# 7seg_Buttons.net
KiCad netlist of a schematic drawn in EAGLE
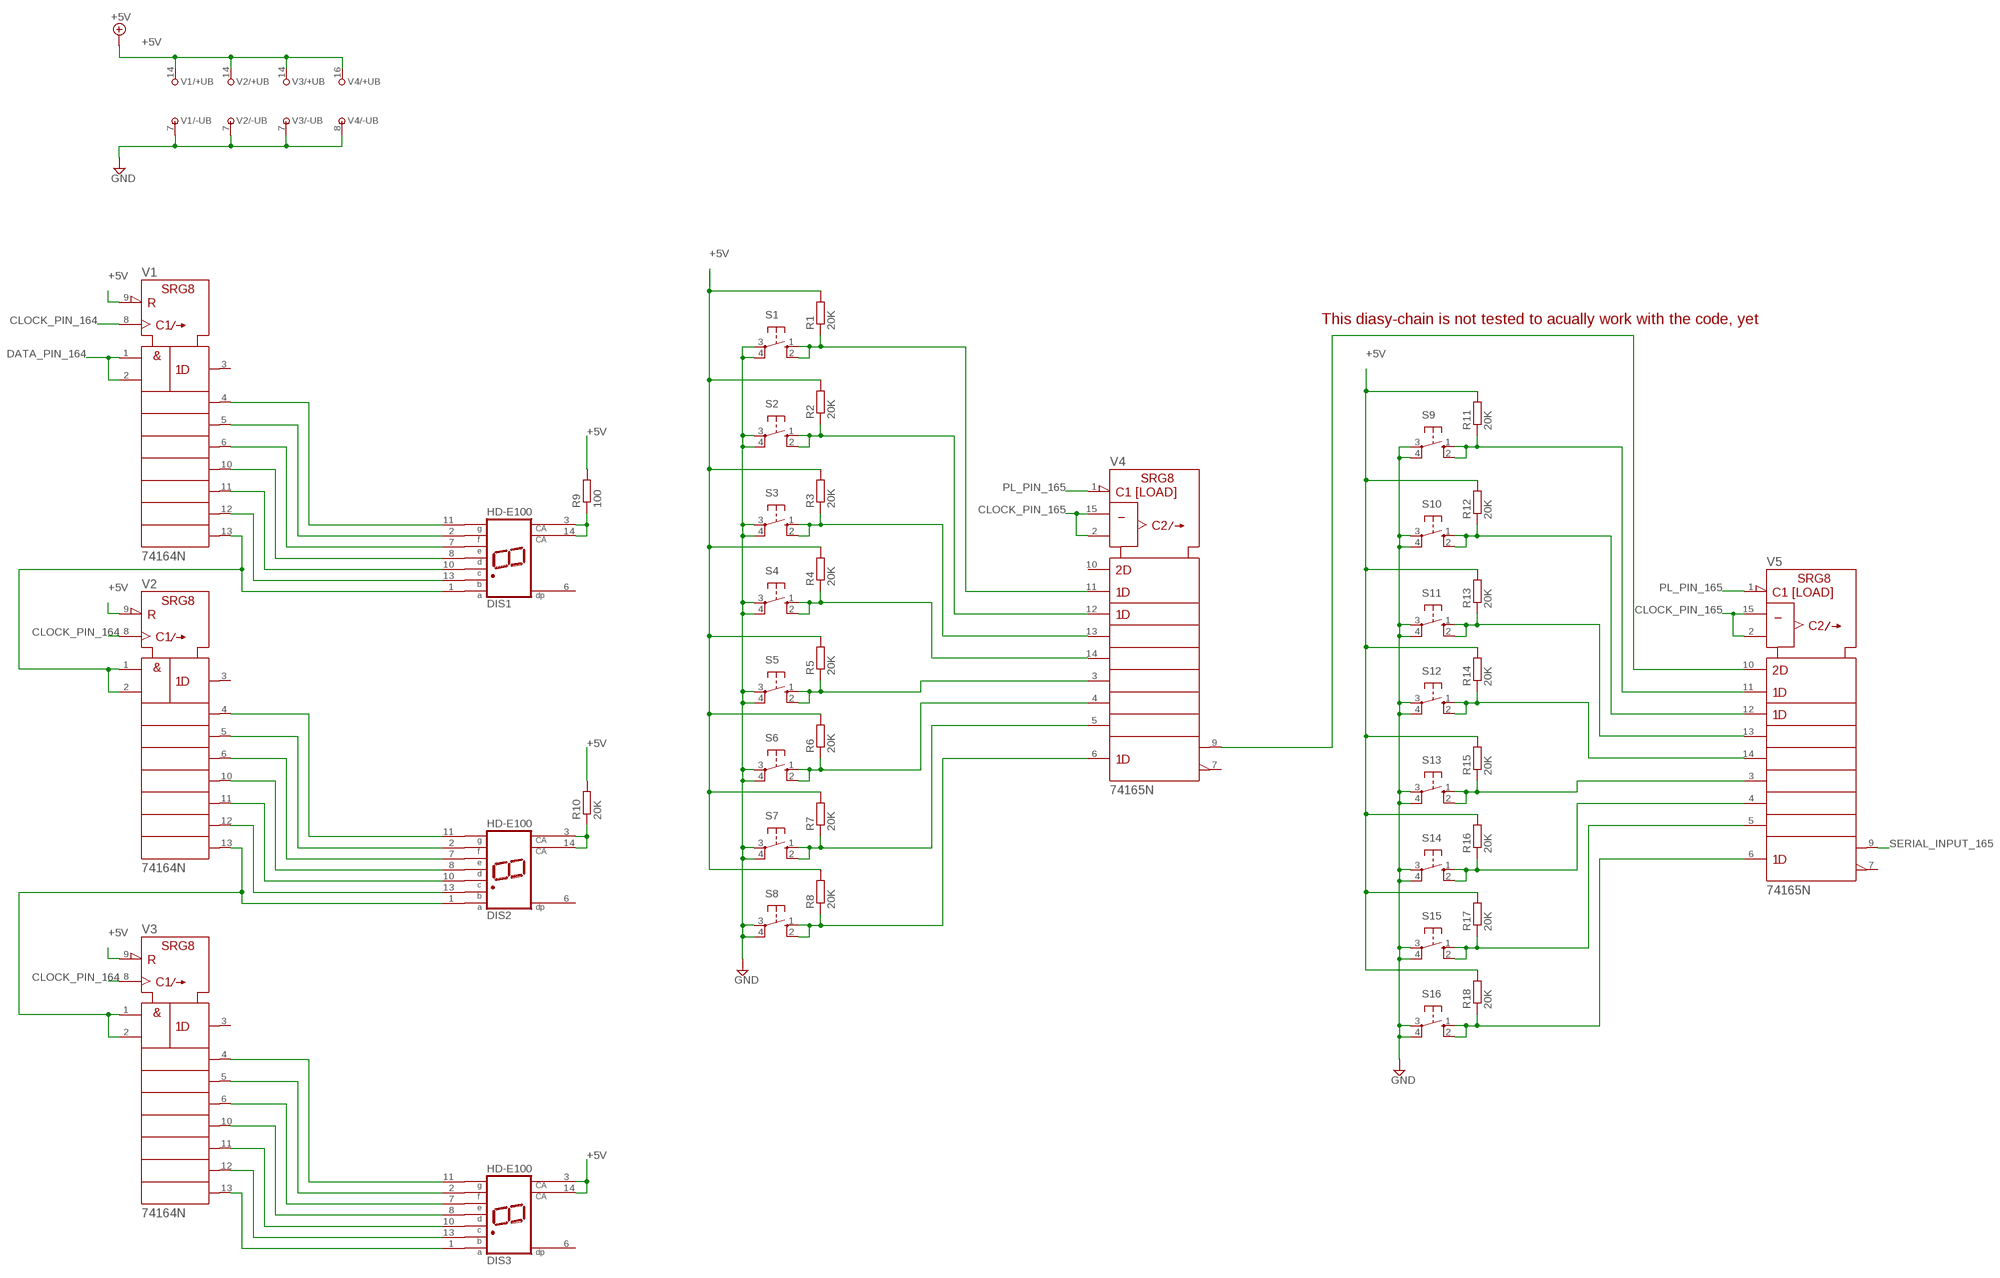
[diagram p0: schematic, sheet 1]

(export (version "E")
  (design (tool "Eeschema 10.0.6"))
  (components
    (comp (ref "DIS1")
      (value "HD-E100")
      (footprint "eagle-import:HDSP-I")
      (libsource (lib "eagle-import") (part "HD-E100"))
    )
    (comp (ref "DIS2")
      (value "HD-E100")
      (footprint "eagle-import:HDSP-I")
      (libsource (lib "eagle-import") (part "HD-E100"))
    )
    (comp (ref "DIS3")
      (value "HD-E100")
      (footprint "eagle-import:HDSP-I")
      (libsource (lib "eagle-import") (part "HD-E100"))
    )
    (comp (ref "R1")
      (value "20K")
      (footprint "eagle-import:0204_7")
      (libsource (lib "eagle-import") (part "R-EU_0204/7"))
    )
    (comp (ref "R2")
      (value "20K")
      (footprint "eagle-import:0204_7")
      (libsource (lib "eagle-import") (part "R-EU_0204/7"))
    )
    (comp (ref "R3")
      (value "20K")
      (footprint "eagle-import:0204_7")
      (libsource (lib "eagle-import") (part "R-EU_0204/7"))
    )
    (comp (ref "R4")
      (value "20K")
      (footprint "eagle-import:0204_7")
      (libsource (lib "eagle-import") (part "R-EU_0204/7"))
    )
    (comp (ref "R5")
      (value "20K")
      (footprint "eagle-import:0204_7")
      (libsource (lib "eagle-import") (part "R-EU_0204/7"))
    )
    (comp (ref "R6")
      (value "20K")
      (footprint "eagle-import:0204_7")
      (libsource (lib "eagle-import") (part "R-EU_0204/7"))
    )
    (comp (ref "R7")
      (value "20K")
      (footprint "eagle-import:0204_7")
      (libsource (lib "eagle-import") (part "R-EU_0204/7"))
    )
    (comp (ref "R8")
      (value "20K")
      (footprint "eagle-import:0204_7")
      (libsource (lib "eagle-import") (part "R-EU_0204/7"))
    )
    (comp (ref "R9")
      (value "100")
      (footprint "eagle-import:0204_7")
      (libsource (lib "eagle-import") (part "R-EU_0204/7"))
    )
    (comp (ref "R10")
      (value "20K")
      (footprint "eagle-import:0204_7")
      (libsource (lib "eagle-import") (part "R-EU_0204/7"))
    )
    (comp (ref "R11")
      (value "20K")
      (footprint "eagle-import:0204_7")
      (libsource (lib "eagle-import") (part "R-EU_0204/7"))
    )
    (comp (ref "R12")
      (value "20K")
      (footprint "eagle-import:0204_7")
      (libsource (lib "eagle-import") (part "R-EU_0204/7"))
    )
    (comp (ref "R13")
      (value "20K")
      (footprint "eagle-import:0204_7")
      (libsource (lib "eagle-import") (part "R-EU_0204/7"))
    )
    (comp (ref "R14")
      (value "20K")
      (footprint "eagle-import:0204_7")
      (libsource (lib "eagle-import") (part "R-EU_0204/7"))
    )
    (comp (ref "R15")
      (value "20K")
      (footprint "eagle-import:0204_7")
      (libsource (lib "eagle-import") (part "R-EU_0204/7"))
    )
    (comp (ref "R16")
      (value "20K")
      (footprint "eagle-import:0204_7")
      (libsource (lib "eagle-import") (part "R-EU_0204/7"))
    )
    (comp (ref "R17")
      (value "20K")
      (footprint "eagle-import:0204_7")
      (libsource (lib "eagle-import") (part "R-EU_0204/7"))
    )
    (comp (ref "R18")
      (value "20K")
      (footprint "eagle-import:0204_7")
      (libsource (lib "eagle-import") (part "R-EU_0204/7"))
    )
    (comp (ref "S1")
      (value "40-XX")
      (footprint "eagle-import:B3F-40XX")
      (fields (field (name "MF") "OMRON COMPONENTS USA") (field (name "MPN") "B3F-4000"))
      (libsource (lib "eagle-import") (part "40-XX"))
    )
    (comp (ref "S2")
      (value "40-XX")
      (footprint "eagle-import:B3F-40XX")
      (fields (field (name "MF") "OMRON COMPONENTS USA") (field (name "MPN") "B3F-4000"))
      (libsource (lib "eagle-import") (part "40-XX"))
    )
    (comp (ref "S3")
      (value "40-XX")
      (footprint "eagle-import:B3F-40XX")
      (fields (field (name "MF") "OMRON COMPONENTS USA") (field (name "MPN") "B3F-4000"))
      (libsource (lib "eagle-import") (part "40-XX"))
    )
    (comp (ref "S4")
      (value "40-XX")
      (footprint "eagle-import:B3F-40XX")
      (fields (field (name "MF") "OMRON COMPONENTS USA") (field (name "MPN") "B3F-4000"))
      (libsource (lib "eagle-import") (part "40-XX"))
    )
    (comp (ref "S5")
      (value "40-XX")
      (footprint "eagle-import:B3F-40XX")
      (fields (field (name "MF") "OMRON COMPONENTS USA") (field (name "MPN") "B3F-4000"))
      (libsource (lib "eagle-import") (part "40-XX"))
    )
    (comp (ref "S6")
      (value "40-XX")
      (footprint "eagle-import:B3F-40XX")
      (fields (field (name "MF") "OMRON COMPONENTS USA") (field (name "MPN") "B3F-4000"))
      (libsource (lib "eagle-import") (part "40-XX"))
    )
    (comp (ref "S7")
      (value "40-XX")
      (footprint "eagle-import:B3F-40XX")
      (fields (field (name "MF") "OMRON COMPONENTS USA") (field (name "MPN") "B3F-4000"))
      (libsource (lib "eagle-import") (part "40-XX"))
    )
    (comp (ref "S8")
      (value "40-XX")
      (footprint "eagle-import:B3F-40XX")
      (fields (field (name "MF") "OMRON COMPONENTS USA") (field (name "MPN") "B3F-4000"))
      (libsource (lib "eagle-import") (part "40-XX"))
    )
    (comp (ref "S9")
      (value "40-XX")
      (footprint "eagle-import:B3F-40XX")
      (fields (field (name "MF") "OMRON COMPONENTS USA") (field (name "MPN") "B3F-4000"))
      (libsource (lib "eagle-import") (part "40-XX"))
    )
    (comp (ref "S10")
      (value "40-XX")
      (footprint "eagle-import:B3F-40XX")
      (fields (field (name "MF") "OMRON COMPONENTS USA") (field (name "MPN") "B3F-4000"))
      (libsource (lib "eagle-import") (part "40-XX"))
    )
    (comp (ref "S11")
      (value "40-XX")
      (footprint "eagle-import:B3F-40XX")
      (fields (field (name "MF") "OMRON COMPONENTS USA") (field (name "MPN") "B3F-4000"))
      (libsource (lib "eagle-import") (part "40-XX"))
    )
    (comp (ref "S12")
      (value "40-XX")
      (footprint "eagle-import:B3F-40XX")
      (fields (field (name "MF") "OMRON COMPONENTS USA") (field (name "MPN") "B3F-4000"))
      (libsource (lib "eagle-import") (part "40-XX"))
    )
    (comp (ref "S13")
      (value "40-XX")
      (footprint "eagle-import:B3F-40XX")
      (fields (field (name "MF") "OMRON COMPONENTS USA") (field (name "MPN") "B3F-4000"))
      (libsource (lib "eagle-import") (part "40-XX"))
    )
    (comp (ref "S14")
      (value "40-XX")
      (footprint "eagle-import:B3F-40XX")
      (fields (field (name "MF") "OMRON COMPONENTS USA") (field (name "MPN") "B3F-4000"))
      (libsource (lib "eagle-import") (part "40-XX"))
    )
    (comp (ref "S15")
      (value "40-XX")
      (footprint "eagle-import:B3F-40XX")
      (fields (field (name "MF") "OMRON COMPONENTS USA") (field (name "MPN") "B3F-4000"))
      (libsource (lib "eagle-import") (part "40-XX"))
    )
    (comp (ref "S16")
      (value "40-XX")
      (footprint "eagle-import:B3F-40XX")
      (fields (field (name "MF") "OMRON COMPONENTS USA") (field (name "MPN") "B3F-4000"))
      (libsource (lib "eagle-import") (part "40-XX"))
    )
    (comp (ref "V1")
      (value "74164N")
      (footprint "eagle-import:DIL14")
      (libsource (lib "eagle-import") (part "74164N"))
    )
    (comp (ref "V2")
      (value "74164N")
      (footprint "eagle-import:DIL14")
      (libsource (lib "eagle-import") (part "74164N"))
    )
    (comp (ref "V3")
      (value "74164N")
      (footprint "eagle-import:DIL14")
      (libsource (lib "eagle-import") (part "74164N"))
    )
    (comp (ref "V4")
      (value "74165N")
      (footprint "eagle-import:DIL16")
      (libsource (lib "eagle-import") (part "74165N"))
    )
    (comp (ref "V5")
      (value "74165N")
      (footprint "eagle-import:DIL16")
      (libsource (lib "eagle-import") (part "74165N"))
    )
  )
  (nets
    (net (code "1") (name "+5V") (class "Default")
      (node (ref "DIS3") (pin "14") (pinfunction "CA_14") (pintype "passive"))
      (node (ref "DIS3") (pin "3") (pinfunction "CA_3") (pintype "passive"))
      (node (ref "R1") (pin "2") (pinfunction "2_2") (pintype "passive"))
      (node (ref "R10") (pin "2") (pinfunction "2_2") (pintype "passive"))
      (node (ref "R11") (pin "2") (pinfunction "2_2") (pintype "passive"))
      (node (ref "R12") (pin "2") (pinfunction "2_2") (pintype "passive"))
      (node (ref "R13") (pin "2") (pinfunction "2_2") (pintype "passive"))
      (node (ref "R14") (pin "2") (pinfunction "2_2") (pintype "passive"))
      (node (ref "R15") (pin "2") (pinfunction "2_2") (pintype "passive"))
      (node (ref "R16") (pin "2") (pinfunction "2_2") (pintype "passive"))
      (node (ref "R17") (pin "2") (pinfunction "2_2") (pintype "passive"))
      (node (ref "R18") (pin "2") (pinfunction "2_2") (pintype "passive"))
      (node (ref "R2") (pin "2") (pinfunction "2_2") (pintype "passive"))
      (node (ref "R3") (pin "2") (pinfunction "2_2") (pintype "passive"))
      (node (ref "R4") (pin "2") (pinfunction "2_2") (pintype "passive"))
      (node (ref "R5") (pin "2") (pinfunction "2_2") (pintype "passive"))
      (node (ref "R6") (pin "2") (pinfunction "2_2") (pintype "passive"))
      (node (ref "R7") (pin "2") (pinfunction "2_2") (pintype "passive"))
      (node (ref "R8") (pin "2") (pinfunction "2_2") (pintype "passive"))
      (node (ref "R9") (pin "2") (pinfunction "2_2") (pintype "passive"))
      (node (ref "V1") (pin "14") (pinfunction "+UB_14") (pintype "power_in"))
      (node (ref "V1") (pin "9") (pinfunction "~{CLR}_9") (pintype "input"))
      (node (ref "V2") (pin "14") (pinfunction "+UB_14") (pintype "power_in"))
      (node (ref "V2") (pin "9") (pinfunction "~{CLR}_9") (pintype "input"))
      (node (ref "V3") (pin "14") (pinfunction "+UB_14") (pintype "power_in"))
      (node (ref "V3") (pin "9") (pinfunction "~{CLR}_9") (pintype "input"))
      (node (ref "V4") (pin "16") (pinfunction "+UB_16") (pintype "power_in"))
    )
    (net (code "2") (name "/CLOCK_PIN_164") (class "Default")
      (node (ref "V1") (pin "8") (pinfunction "CLK_8") (pintype "input"))
      (node (ref "V2") (pin "8") (pinfunction "CLK_8") (pintype "input"))
      (node (ref "V3") (pin "8") (pinfunction "CLK_8") (pintype "input"))
    )
    (net (code "3") (name "/CLOCK_PIN_165") (class "Default")
      (node (ref "V4") (pin "15") (pinfunction "CLK_INH_15") (pintype "input"))
      (node (ref "V4") (pin "2") (pinfunction "CLK_2") (pintype "input"))
      (node (ref "V5") (pin "15") (pinfunction "CLK_INH_15") (pintype "input"))
      (node (ref "V5") (pin "2") (pinfunction "CLK_2") (pintype "input"))
    )
    (net (code "4") (name "/DATA_PIN_164") (class "Default")
      (node (ref "V1") (pin "1") (pinfunction "A_1") (pintype "input"))
      (node (ref "V1") (pin "2") (pinfunction "B_2") (pintype "input"))
    )
    (net (code "5") (name "/PL_PIN_165") (class "Default")
      (node (ref "V4") (pin "1") (pinfunction "SH/~{LD}_1") (pintype "input"))
      (node (ref "V5") (pin "1") (pinfunction "SH/~{LD}_1") (pintype "input"))
    )
    (net (code "6") (name "/SERIAL_INPUT_165") (class "Default")
      (node (ref "V5") (pin "9") (pinfunction "QH_9") (pintype "output"))
    )
    (net (code "7") (name "GND") (class "Default")
      (node (ref "S1") (pin "3") (pinfunction "P_3") (pintype "passive"))
      (node (ref "S1") (pin "4") (pinfunction "P1_4") (pintype "passive"))
      (node (ref "S10") (pin "3") (pinfunction "P_3") (pintype "passive"))
      (node (ref "S10") (pin "4") (pinfunction "P1_4") (pintype "passive"))
      (node (ref "S11") (pin "3") (pinfunction "P_3") (pintype "passive"))
      (node (ref "S11") (pin "4") (pinfunction "P1_4") (pintype "passive"))
      (node (ref "S12") (pin "3") (pinfunction "P_3") (pintype "passive"))
      (node (ref "S12") (pin "4") (pinfunction "P1_4") (pintype "passive"))
      (node (ref "S13") (pin "3") (pinfunction "P_3") (pintype "passive"))
      (node (ref "S13") (pin "4") (pinfunction "P1_4") (pintype "passive"))
      (node (ref "S14") (pin "3") (pinfunction "P_3") (pintype "passive"))
      (node (ref "S14") (pin "4") (pinfunction "P1_4") (pintype "passive"))
      (node (ref "S15") (pin "3") (pinfunction "P_3") (pintype "passive"))
      (node (ref "S15") (pin "4") (pinfunction "P1_4") (pintype "passive"))
      (node (ref "S16") (pin "3") (pinfunction "P_3") (pintype "passive"))
      (node (ref "S16") (pin "4") (pinfunction "P1_4") (pintype "passive"))
      (node (ref "S2") (pin "3") (pinfunction "P_3") (pintype "passive"))
      (node (ref "S2") (pin "4") (pinfunction "P1_4") (pintype "passive"))
      (node (ref "S3") (pin "3") (pinfunction "P_3") (pintype "passive"))
      (node (ref "S3") (pin "4") (pinfunction "P1_4") (pintype "passive"))
      (node (ref "S4") (pin "3") (pinfunction "P_3") (pintype "passive"))
      (node (ref "S4") (pin "4") (pinfunction "P1_4") (pintype "passive"))
      (node (ref "S5") (pin "3") (pinfunction "P_3") (pintype "passive"))
      (node (ref "S5") (pin "4") (pinfunction "P1_4") (pintype "passive"))
      (node (ref "S6") (pin "3") (pinfunction "P_3") (pintype "passive"))
      (node (ref "S6") (pin "4") (pinfunction "P1_4") (pintype "passive"))
      (node (ref "S7") (pin "3") (pinfunction "P_3") (pintype "passive"))
      (node (ref "S7") (pin "4") (pinfunction "P1_4") (pintype "passive"))
      (node (ref "S8") (pin "3") (pinfunction "P_3") (pintype "passive"))
      (node (ref "S8") (pin "4") (pinfunction "P1_4") (pintype "passive"))
      (node (ref "S9") (pin "3") (pinfunction "P_3") (pintype "passive"))
      (node (ref "S9") (pin "4") (pinfunction "P1_4") (pintype "passive"))
      (node (ref "V1") (pin "7") (pinfunction "-UB_7") (pintype "power_in"))
      (node (ref "V2") (pin "7") (pinfunction "-UB_7") (pintype "power_in"))
      (node (ref "V3") (pin "7") (pinfunction "-UB_7") (pintype "power_in"))
      (node (ref "V4") (pin "8") (pinfunction "-UB_8") (pintype "power_in"))
    )
    (net (code "8") (name "Net-(DIS1-A)") (class "Default")
      (node (ref "DIS1") (pin "1") (pinfunction "A_1") (pintype "passive"))
      (node (ref "V1") (pin "13") (pinfunction "QH_13") (pintype "output"))
      (node (ref "V2") (pin "1") (pinfunction "A_1") (pintype "input"))
      (node (ref "V2") (pin "2") (pinfunction "B_2") (pintype "input"))
    )
    (net (code "9") (name "Net-(DIS1-B)") (class "Default")
      (node (ref "DIS1") (pin "13") (pinfunction "B_13") (pintype "passive"))
      (node (ref "V1") (pin "12") (pinfunction "QG_12") (pintype "output"))
    )
    (net (code "10") (name "Net-(DIS1-C)") (class "Default")
      (node (ref "DIS1") (pin "10") (pinfunction "C_10") (pintype "passive"))
      (node (ref "V1") (pin "11") (pinfunction "QF_11") (pintype "output"))
    )
    (net (code "11") (name "Net-(DIS1-CA-Pad14)") (class "Default")
      (node (ref "DIS1") (pin "14") (pinfunction "CA_14") (pintype "passive"))
      (node (ref "DIS1") (pin "3") (pinfunction "CA_3") (pintype "passive"))
      (node (ref "R9") (pin "1") (pinfunction "1_1") (pintype "passive"))
    )
    (net (code "12") (name "Net-(DIS1-D)") (class "Default")
      (node (ref "DIS1") (pin "8") (pinfunction "D_8") (pintype "passive"))
      (node (ref "V1") (pin "10") (pinfunction "QE_10") (pintype "output"))
    )
    (net (code "13") (name "Net-(DIS1-E)") (class "Default")
      (node (ref "DIS1") (pin "7") (pinfunction "E_7") (pintype "passive"))
      (node (ref "V1") (pin "6") (pinfunction "QD_6") (pintype "output"))
    )
    (net (code "14") (name "Net-(DIS1-F)") (class "Default")
      (node (ref "DIS1") (pin "2") (pinfunction "F_2") (pintype "passive"))
      (node (ref "V1") (pin "5") (pinfunction "QC_5") (pintype "output"))
    )
    (net (code "15") (name "Net-(DIS1-G)") (class "Default")
      (node (ref "DIS1") (pin "11") (pinfunction "G_11") (pintype "passive"))
      (node (ref "V1") (pin "4") (pinfunction "QB_4") (pintype "output"))
    )
    (net (code "16") (name "Net-(DIS2-A)") (class "Default")
      (node (ref "DIS2") (pin "1") (pinfunction "A_1") (pintype "passive"))
      (node (ref "V2") (pin "13") (pinfunction "QH_13") (pintype "output"))
      (node (ref "V3") (pin "1") (pinfunction "A_1") (pintype "input"))
      (node (ref "V3") (pin "2") (pinfunction "B_2") (pintype "input"))
    )
    (net (code "17") (name "Net-(DIS2-B)") (class "Default")
      (node (ref "DIS2") (pin "13") (pinfunction "B_13") (pintype "passive"))
      (node (ref "V2") (pin "12") (pinfunction "QG_12") (pintype "output"))
    )
    (net (code "18") (name "Net-(DIS2-C)") (class "Default")
      (node (ref "DIS2") (pin "10") (pinfunction "C_10") (pintype "passive"))
      (node (ref "V2") (pin "11") (pinfunction "QF_11") (pintype "output"))
    )
    (net (code "19") (name "Net-(DIS2-CA-Pad14)") (class "Default")
      (node (ref "DIS2") (pin "14") (pinfunction "CA_14") (pintype "passive"))
      (node (ref "DIS2") (pin "3") (pinfunction "CA_3") (pintype "passive"))
      (node (ref "R10") (pin "1") (pinfunction "1_1") (pintype "passive"))
    )
    (net (code "20") (name "Net-(DIS2-D)") (class "Default")
      (node (ref "DIS2") (pin "8") (pinfunction "D_8") (pintype "passive"))
      (node (ref "V2") (pin "10") (pinfunction "QE_10") (pintype "output"))
    )
    (net (code "21") (name "Net-(DIS2-E)") (class "Default")
      (node (ref "DIS2") (pin "7") (pinfunction "E_7") (pintype "passive"))
      (node (ref "V2") (pin "6") (pinfunction "QD_6") (pintype "output"))
    )
    (net (code "22") (name "Net-(DIS2-F)") (class "Default")
      (node (ref "DIS2") (pin "2") (pinfunction "F_2") (pintype "passive"))
      (node (ref "V2") (pin "5") (pinfunction "QC_5") (pintype "output"))
    )
    (net (code "23") (name "Net-(DIS2-G)") (class "Default")
      (node (ref "DIS2") (pin "11") (pinfunction "G_11") (pintype "passive"))
      (node (ref "V2") (pin "4") (pinfunction "QB_4") (pintype "output"))
    )
    (net (code "24") (name "Net-(DIS3-A)") (class "Default")
      (node (ref "DIS3") (pin "1") (pinfunction "A_1") (pintype "passive"))
      (node (ref "V3") (pin "13") (pinfunction "QH_13") (pintype "output"))
    )
    (net (code "25") (name "Net-(DIS3-B)") (class "Default")
      (node (ref "DIS3") (pin "13") (pinfunction "B_13") (pintype "passive"))
      (node (ref "V3") (pin "12") (pinfunction "QG_12") (pintype "output"))
    )
    (net (code "26") (name "Net-(DIS3-C)") (class "Default")
      (node (ref "DIS3") (pin "10") (pinfunction "C_10") (pintype "passive"))
      (node (ref "V3") (pin "11") (pinfunction "QF_11") (pintype "output"))
    )
    (net (code "27") (name "Net-(DIS3-D)") (class "Default")
      (node (ref "DIS3") (pin "8") (pinfunction "D_8") (pintype "passive"))
      (node (ref "V3") (pin "10") (pinfunction "QE_10") (pintype "output"))
    )
    (net (code "28") (name "Net-(DIS3-E)") (class "Default")
      (node (ref "DIS3") (pin "7") (pinfunction "E_7") (pintype "passive"))
      (node (ref "V3") (pin "6") (pinfunction "QD_6") (pintype "output"))
    )
    (net (code "29") (name "Net-(DIS3-F)") (class "Default")
      (node (ref "DIS3") (pin "2") (pinfunction "F_2") (pintype "passive"))
      (node (ref "V3") (pin "5") (pinfunction "QC_5") (pintype "output"))
    )
    (net (code "30") (name "Net-(DIS3-G)") (class "Default")
      (node (ref "DIS3") (pin "11") (pinfunction "G_11") (pintype "passive"))
      (node (ref "V3") (pin "4") (pinfunction "QB_4") (pintype "output"))
    )
    (net (code "31") (name "Net-(S1-S)") (class "Default")
      (node (ref "R1") (pin "1") (pinfunction "1_1") (pintype "passive"))
      (node (ref "S1") (pin "1") (pinfunction "S_1") (pintype "passive"))
      (node (ref "S1") (pin "2") (pinfunction "S1_2") (pintype "passive"))
      (node (ref "V4") (pin "11") (pinfunction "A_11") (pintype "input"))
    )
    (net (code "32") (name "Net-(S2-S)") (class "Default")
      (node (ref "R2") (pin "1") (pinfunction "1_1") (pintype "passive"))
      (node (ref "S2") (pin "1") (pinfunction "S_1") (pintype "passive"))
      (node (ref "S2") (pin "2") (pinfunction "S1_2") (pintype "passive"))
      (node (ref "V4") (pin "12") (pinfunction "B_12") (pintype "input"))
    )
    (net (code "33") (name "Net-(S3-S)") (class "Default")
      (node (ref "R3") (pin "1") (pinfunction "1_1") (pintype "passive"))
      (node (ref "S3") (pin "1") (pinfunction "S_1") (pintype "passive"))
      (node (ref "S3") (pin "2") (pinfunction "S1_2") (pintype "passive"))
      (node (ref "V4") (pin "13") (pinfunction "C_13") (pintype "input"))
    )
    (net (code "34") (name "Net-(S4-S)") (class "Default")
      (node (ref "R4") (pin "1") (pinfunction "1_1") (pintype "passive"))
      (node (ref "S4") (pin "1") (pinfunction "S_1") (pintype "passive"))
      (node (ref "S4") (pin "2") (pinfunction "S1_2") (pintype "passive"))
      (node (ref "V4") (pin "14") (pinfunction "D_14") (pintype "input"))
    )
    (net (code "35") (name "Net-(S5-S)") (class "Default")
      (node (ref "R5") (pin "1") (pinfunction "1_1") (pintype "passive"))
      (node (ref "S5") (pin "1") (pinfunction "S_1") (pintype "passive"))
      (node (ref "S5") (pin "2") (pinfunction "S1_2") (pintype "passive"))
      (node (ref "V4") (pin "3") (pinfunction "E_3") (pintype "input"))
    )
    (net (code "36") (name "Net-(S6-S)") (class "Default")
      (node (ref "R6") (pin "1") (pinfunction "1_1") (pintype "passive"))
      (node (ref "S6") (pin "1") (pinfunction "S_1") (pintype "passive"))
      (node (ref "S6") (pin "2") (pinfunction "S1_2") (pintype "passive"))
      (node (ref "V4") (pin "4") (pinfunction "F_4") (pintype "input"))
    )
    (net (code "37") (name "Net-(S7-S)") (class "Default")
      (node (ref "R7") (pin "1") (pinfunction "1_1") (pintype "passive"))
      (node (ref "S7") (pin "1") (pinfunction "S_1") (pintype "passive"))
      (node (ref "S7") (pin "2") (pinfunction "S1_2") (pintype "passive"))
      (node (ref "V4") (pin "5") (pinfunction "G_5") (pintype "input"))
    )
    (net (code "38") (name "Net-(S8-S)") (class "Default")
      (node (ref "R8") (pin "1") (pinfunction "1_1") (pintype "passive"))
      (node (ref "S8") (pin "1") (pinfunction "S_1") (pintype "passive"))
      (node (ref "S8") (pin "2") (pinfunction "S1_2") (pintype "passive"))
      (node (ref "V4") (pin "6") (pinfunction "H_6") (pintype "input"))
    )
    (net (code "39") (name "Net-(S9-S)") (class "Default")
      (node (ref "R11") (pin "1") (pinfunction "1_1") (pintype "passive"))
      (node (ref "S9") (pin "1") (pinfunction "S_1") (pintype "passive"))
      (node (ref "S9") (pin "2") (pinfunction "S1_2") (pintype "passive"))
      (node (ref "V5") (pin "11") (pinfunction "A_11") (pintype "input"))
    )
    (net (code "40") (name "Net-(S10-S)") (class "Default")
      (node (ref "R12") (pin "1") (pinfunction "1_1") (pintype "passive"))
      (node (ref "S10") (pin "1") (pinfunction "S_1") (pintype "passive"))
      (node (ref "S10") (pin "2") (pinfunction "S1_2") (pintype "passive"))
      (node (ref "V5") (pin "12") (pinfunction "B_12") (pintype "input"))
    )
    (net (code "41") (name "Net-(S11-S)") (class "Default")
      (node (ref "R13") (pin "1") (pinfunction "1_1") (pintype "passive"))
      (node (ref "S11") (pin "1") (pinfunction "S_1") (pintype "passive"))
      (node (ref "S11") (pin "2") (pinfunction "S1_2") (pintype "passive"))
      (node (ref "V5") (pin "13") (pinfunction "C_13") (pintype "input"))
    )
    (net (code "42") (name "Net-(S12-S)") (class "Default")
      (node (ref "R14") (pin "1") (pinfunction "1_1") (pintype "passive"))
      (node (ref "S12") (pin "1") (pinfunction "S_1") (pintype "passive"))
      (node (ref "S12") (pin "2") (pinfunction "S1_2") (pintype "passive"))
      (node (ref "V5") (pin "14") (pinfunction "D_14") (pintype "input"))
    )
    (net (code "43") (name "Net-(S13-S)") (class "Default")
      (node (ref "R15") (pin "1") (pinfunction "1_1") (pintype "passive"))
      (node (ref "S13") (pin "1") (pinfunction "S_1") (pintype "passive"))
      (node (ref "S13") (pin "2") (pinfunction "S1_2") (pintype "passive"))
      (node (ref "V5") (pin "3") (pinfunction "E_3") (pintype "input"))
    )
    (net (code "44") (name "Net-(S14-S)") (class "Default")
      (node (ref "R16") (pin "1") (pinfunction "1_1") (pintype "passive"))
      (node (ref "S14") (pin "1") (pinfunction "S_1") (pintype "passive"))
      (node (ref "S14") (pin "2") (pinfunction "S1_2") (pintype "passive"))
      (node (ref "V5") (pin "4") (pinfunction "F_4") (pintype "input"))
    )
    (net (code "45") (name "Net-(S15-S)") (class "Default")
      (node (ref "R17") (pin "1") (pinfunction "1_1") (pintype "passive"))
      (node (ref "S15") (pin "1") (pinfunction "S_1") (pintype "passive"))
      (node (ref "S15") (pin "2") (pinfunction "S1_2") (pintype "passive"))
      (node (ref "V5") (pin "5") (pinfunction "G_5") (pintype "input"))
    )
    (net (code "46") (name "Net-(S16-S)") (class "Default")
      (node (ref "R18") (pin "1") (pinfunction "1_1") (pintype "passive"))
      (node (ref "S16") (pin "1") (pinfunction "S_1") (pintype "passive"))
      (node (ref "S16") (pin "2") (pinfunction "S1_2") (pintype "passive"))
      (node (ref "V5") (pin "6") (pinfunction "H_6") (pintype "input"))
    )
    (net (code "47") (name "Net-(V4C-QH)") (class "Default")
      (node (ref "V4") (pin "9") (pinfunction "QH_9") (pintype "output"))
      (node (ref "V5") (pin "10") (pinfunction "SER_10") (pintype "input"))
    )
    (net (code "48") (name "unconnected-(DIS1-DP-Pad6)") (class "Default")
      (node (ref "DIS1") (pin "6") (pinfunction "DP_6") (pintype "passive"))
    )
    (net (code "49") (name "unconnected-(DIS2-DP-Pad6)") (class "Default")
      (node (ref "DIS2") (pin "6") (pinfunction "DP_6") (pintype "passive"))
    )
    (net (code "50") (name "unconnected-(DIS3-DP-Pad6)") (class "Default")
      (node (ref "DIS3") (pin "6") (pinfunction "DP_6") (pintype "passive"))
    )
    (net (code "51") (name "unconnected-(V1C-QA-Pad3)") (class "Default")
      (node (ref "V1") (pin "3") (pinfunction "QA_3") (pintype "output"))
    )
    (net (code "52") (name "unconnected-(V2C-QA-Pad3)") (class "Default")
      (node (ref "V2") (pin "3") (pinfunction "QA_3") (pintype "output"))
    )
    (net (code "53") (name "unconnected-(V3C-QA-Pad3)") (class "Default")
      (node (ref "V3") (pin "3") (pinfunction "QA_3") (pintype "output"))
    )
    (net (code "54") (name "unconnected-(V4C-SER-Pad10)") (class "Default")
      (node (ref "V4") (pin "10") (pinfunction "SER_10") (pintype "input"))
    )
    (net (code "55") (name "unconnected-(V4C-~{QH}-Pad7)") (class "Default")
      (node (ref "V4") (pin "7") (pinfunction "~{QH}_7") (pintype "output"))
    )
    (net (code "56") (name "unconnected-(V5C-~{QH}-Pad7)") (class "Default")
      (node (ref "V5") (pin "7") (pinfunction "~{QH}_7") (pintype "output"))
    )
  )
)
